# Adapter-OBD_12V5VDCDC.net
KiCad netlist of a schematic drawn in EasyEDA
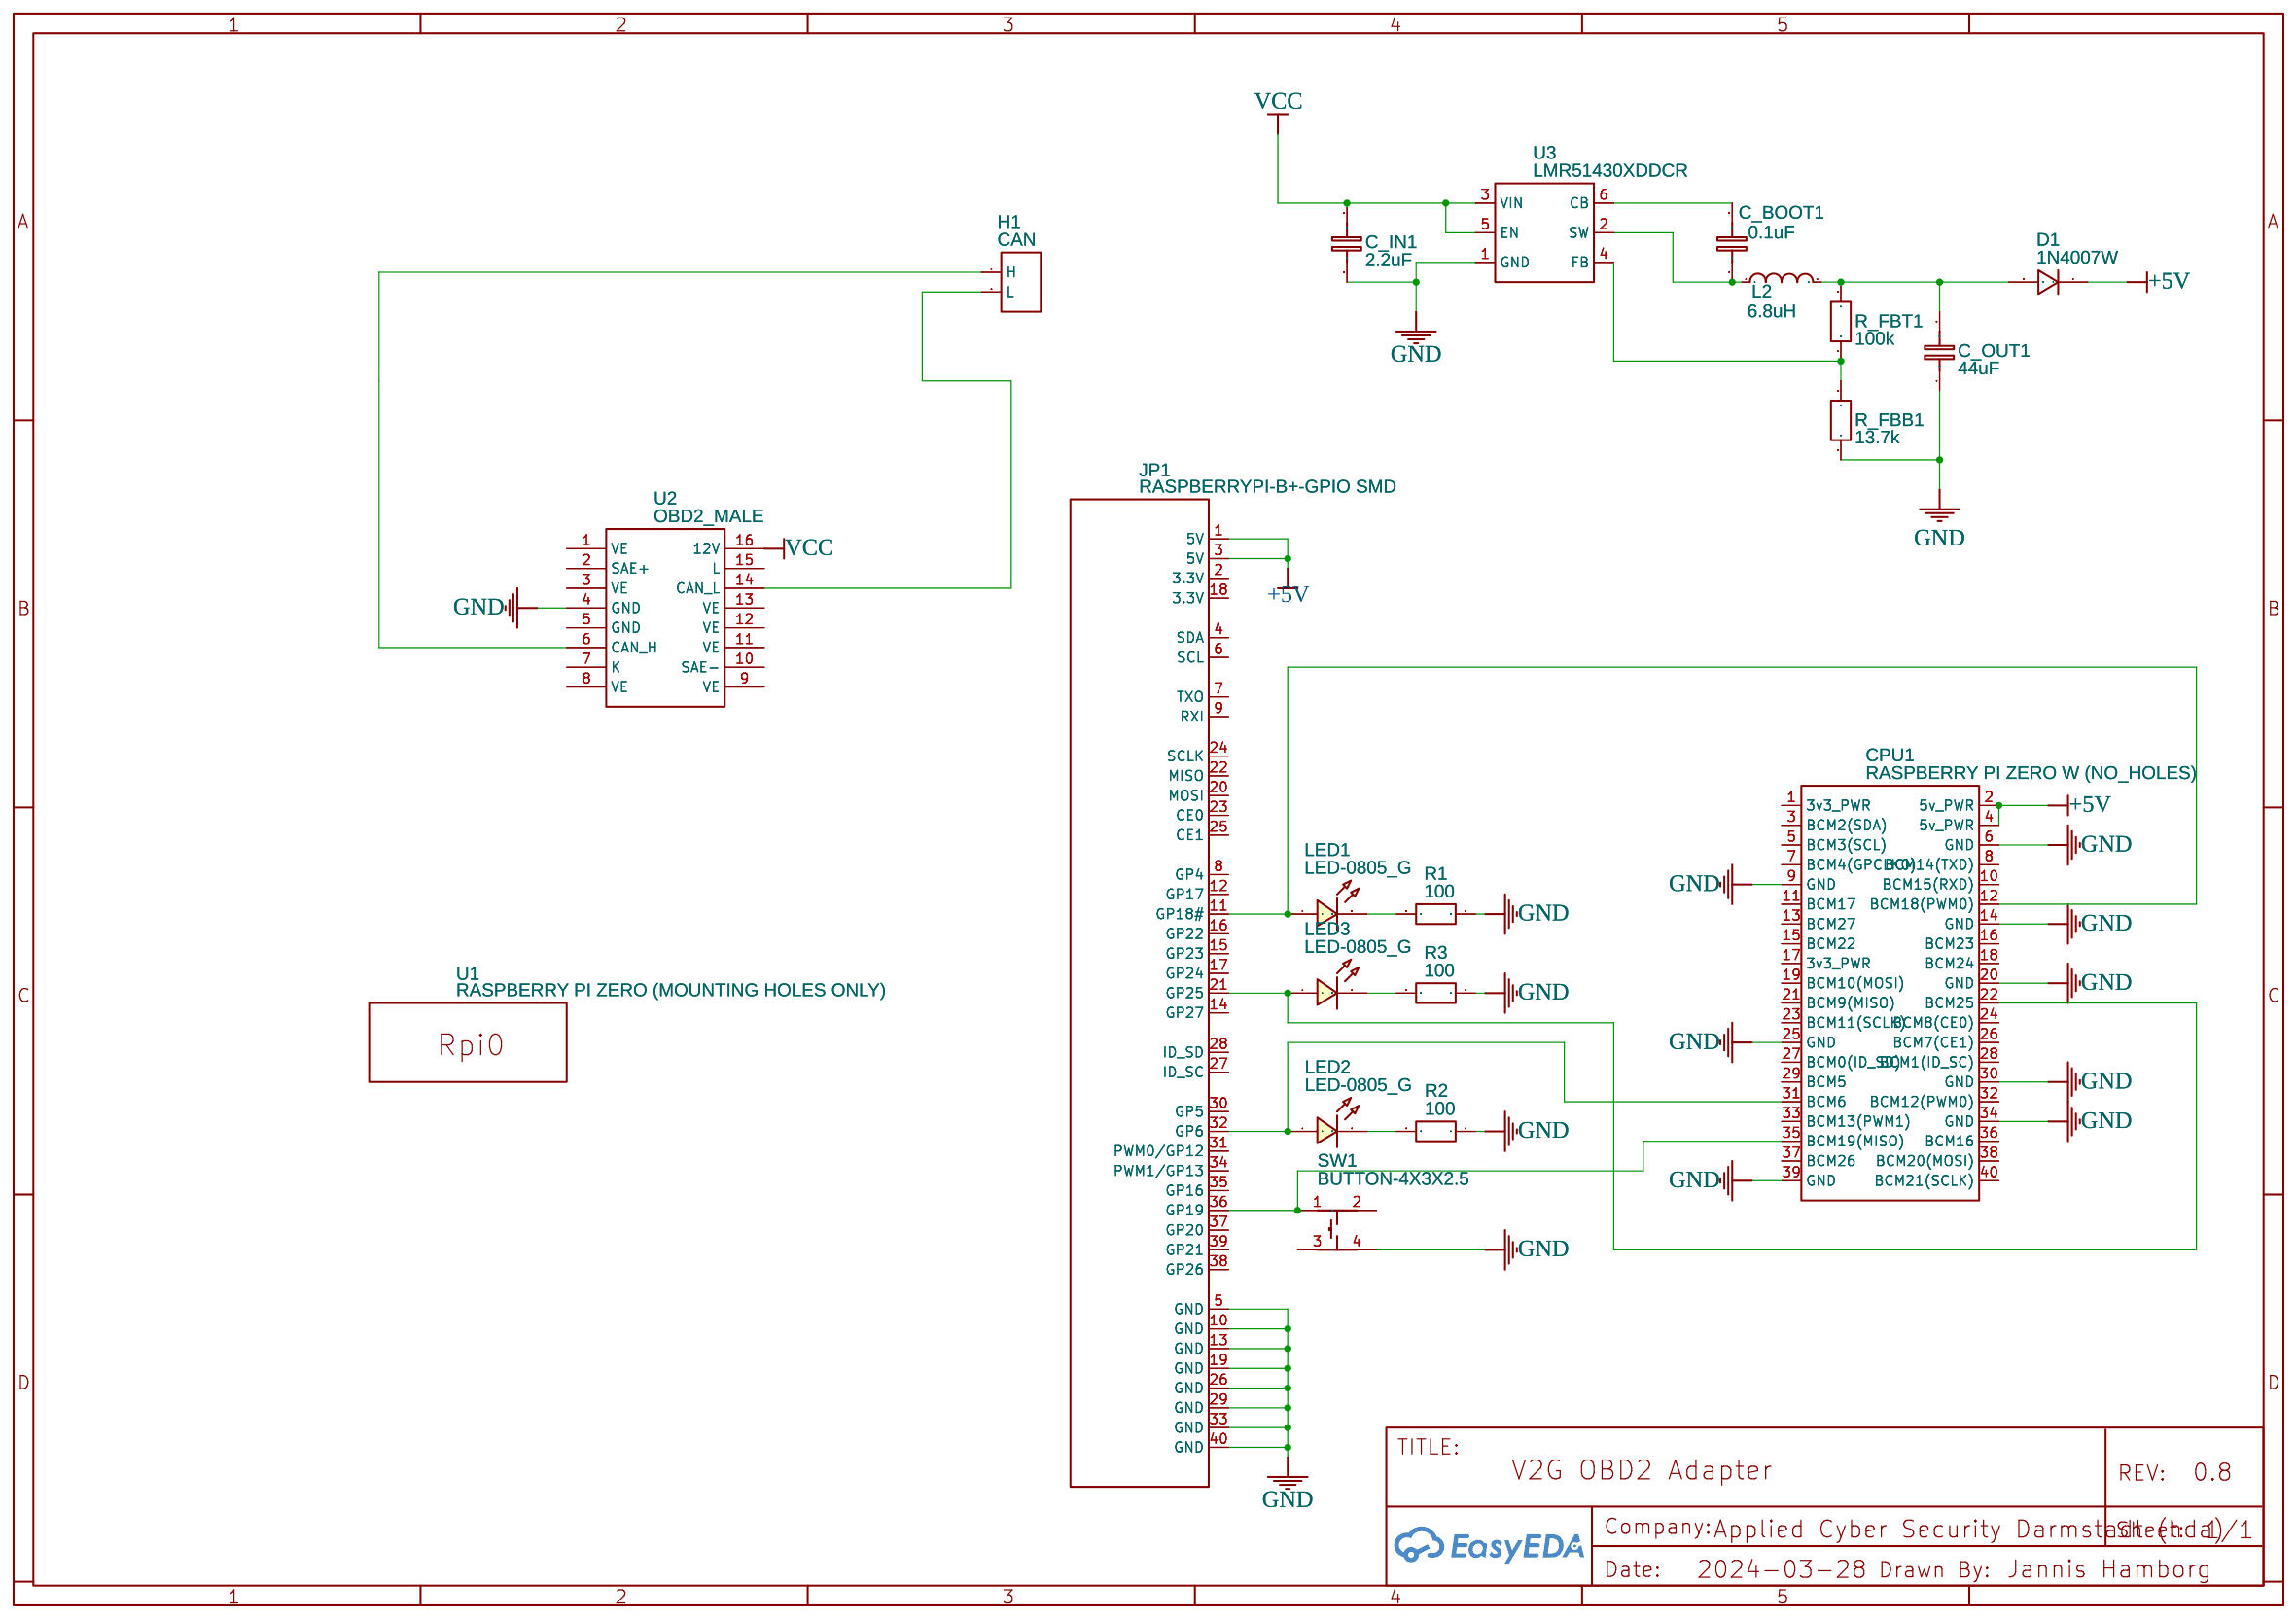
[diagram p0: schematic sheet]

(export (version "E")
  (design (tool "Eeschema 10.0.6"))
  (components
    (comp (ref "CPU1")
      (value "RASPBERRY PI ZERO W (NO_HOLES)")
      (fields (field (name "Manufacturer Part") "Pi Zero W") (field (name "Manufacturer") "Raspberry Pi"))
      (libsource (lib "") (part "RASPBERRY PI ZERO W (NO_HOLES)"))
    )
    (comp (ref "C_BOOT1") (value "0.1uF") (libsource (lib "") (part "C_0805_EU")))
    (comp (ref "C_IN1") (value "2.2uF") (libsource (lib "") (part "C_0805_EU_2")))
    (comp (ref "C_OUT1") (value "44uF") (libsource (lib "") (part "C_0805_EU_1")))
    (comp (ref "D1")
      (value "1N4007W")
      (fields (field (name "Manufacturer") "BLUE ROCKET"))
      (libsource (lib "") (part "1N4007W"))
    )
    (comp (ref "H1") (value "CAN") (libsource (lib "") (part "HDR-F-2.54_1x2")))
    (comp (ref "JP1")
      (value "RASPBERRYPI-B+-GPIO SMD")
      (fields
        (field (name "Manufacturer Part") "95157-440LF")
        (field (name "Manufacturer") "Amphenol ICC (FCI)")
      )
      (libsource (lib "") (part "RASPBERRYPI-B+-GPIO SMD"))
    )
    (comp (ref "L2")
      (value "6.8uH")
      (fields (field (name "Manufacturer Part") "FHW0805UF6R8JST") (field (name "Manufacturer") "FH(风华)"))
      (libsource (lib "") (part "FHW0805UF6R8JST"))
    )
    (comp (ref "LED1")
      (value "LED-0805_G")
      (fields (field (name "Manufacturer Part") "NCD0805G1") (field (name "Manufacturer") "国星光电"))
      (libsource (lib "") (part "LED-0805_G"))
    )
    (comp (ref "LED2")
      (value "LED-0805_G")
      (fields (field (name "Manufacturer Part") "NCD0805G1") (field (name "Manufacturer") "国星光电"))
      (libsource (lib "") (part "LED-0805_G"))
    )
    (comp (ref "LED3")
      (value "LED-0805_G")
      (fields (field (name "Manufacturer Part") "NCD0805G1") (field (name "Manufacturer") "国星光电"))
      (libsource (lib "") (part "LED-0805_G"))
    )
    (comp (ref "R1") (value "100") (libsource (lib "") (part "R_0805_EU_1")))
    (comp (ref "R2") (value "100") (libsource (lib "") (part "R_0805_EU")))
    (comp (ref "R3") (value "100") (libsource (lib "") (part "R_0805_EU")))
    (comp (ref "R_FBB1") (value "13.7k") (libsource (lib "") (part "R_0603_EU")))
    (comp (ref "R_FBT1") (value "100k") (libsource (lib "") (part "R_0603_EU_1")))
    (comp (ref "SW1") (value "BUTTON-4X3X2.5") (libsource (lib "") (part "BUTTON-4X3X2.5")))
    (comp (ref "U1")
      (value "RASPBERRY PI ZERO (MOUNTING HOLES ONLY)")
      (fields (field (name "Manufacturer Part") "Raspberry Pi Zero W"))
      (libsource (lib "") (part "RASPBERRY PI ZERO (MOUNTING HOLES ONLY)"))
    )
    (comp (ref "U2") (value "OBD2_MALE") (libsource (lib "") (part "OBD2_MALE")))
    (comp (ref "U3") (value "LMR51430XDDCR") (libsource (lib "") (part "LMR51430XDDCR")))
  )
  (nets
    (net (code "1") (name "+5V") (class "Default")
      (node (ref "CPU1") (pin "2") (pinfunction "5v_PWR_2") (pintype "unspecified"))
      (node (ref "CPU1") (pin "4") (pinfunction "5v_PWR_4") (pintype "unspecified"))
      (node (ref "D1") (pin "1") (pinfunction "1_1") (pintype "unspecified"))
      (node (ref "JP1") (pin "1") (pinfunction "5V_1") (pintype "passive"))
      (node (ref "JP1") (pin "3") (pinfunction "5V_3") (pintype "passive"))
    )
    (net (code "2") (name "GND") (class "Default")
      (node (ref "CPU1") (pin "14") (pinfunction "GND_14") (pintype "unspecified"))
      (node (ref "CPU1") (pin "20") (pinfunction "GND_20") (pintype "unspecified"))
      (node (ref "CPU1") (pin "25") (pinfunction "GND_25") (pintype "unspecified"))
      (node (ref "CPU1") (pin "30") (pinfunction "GND_30") (pintype "unspecified"))
      (node (ref "CPU1") (pin "34") (pinfunction "GND_34") (pintype "unspecified"))
      (node (ref "CPU1") (pin "39") (pinfunction "GND_39") (pintype "unspecified"))
      (node (ref "CPU1") (pin "6") (pinfunction "GND_6") (pintype "unspecified"))
      (node (ref "CPU1") (pin "9") (pinfunction "GND_9") (pintype "unspecified"))
      (node (ref "C_IN1") (pin "1") (pinfunction "1_1") (pintype "unspecified"))
      (node (ref "C_OUT1") (pin "1") (pinfunction "1_1") (pintype "unspecified"))
      (node (ref "JP1") (pin "10") (pinfunction "GND_10") (pintype "passive"))
      (node (ref "JP1") (pin "13") (pinfunction "GND_13") (pintype "passive"))
      (node (ref "JP1") (pin "19") (pinfunction "GND_19") (pintype "passive"))
      (node (ref "JP1") (pin "26") (pinfunction "GND_26") (pintype "passive"))
      (node (ref "JP1") (pin "29") (pinfunction "GND_29") (pintype "passive"))
      (node (ref "JP1") (pin "33") (pinfunction "GND_33") (pintype "passive"))
      (node (ref "JP1") (pin "40") (pinfunction "GND_40") (pintype "passive"))
      (node (ref "JP1") (pin "5") (pinfunction "GND_5") (pintype "passive"))
      (node (ref "R1") (pin "2") (pinfunction "2_2") (pintype "unspecified"))
      (node (ref "R2") (pin "1") (pinfunction "1_1") (pintype "unspecified"))
      (node (ref "R3") (pin "1") (pinfunction "1_1") (pintype "unspecified"))
      (node (ref "R_FBB1") (pin "1") (pinfunction "1_1") (pintype "unspecified"))
      (node (ref "SW1") (pin "4") (pinfunction "4_4") (pintype "unspecified"))
      (node (ref "U2") (pin "4") (pinfunction "GND_4") (pintype "unspecified"))
      (node (ref "U3") (pin "1") (pinfunction "GND_1") (pintype "unspecified"))
    )
    (net (code "3") (name "Net-(CPU1-BCM6)") (class "Default")
      (node (ref "CPU1") (pin "31") (pinfunction "BCM6_31") (pintype "unspecified"))
      (node (ref "JP1") (pin "32") (pinfunction "GP6_32") (pintype "unspecified"))
      (node (ref "LED2") (pin "1") (pinfunction "1_1") (pintype "unspecified"))
    )
    (net (code "4") (name "Net-(CPU1-BCM18(PWM0))") (class "Default")
      (node (ref "CPU1") (pin "12") (pinfunction "BCM18(PWM0)_12") (pintype "unspecified"))
      (node (ref "JP1") (pin "11") (pinfunction "GP18#_11") (pintype "unspecified"))
      (node (ref "LED1") (pin "1") (pinfunction "1_1") (pintype "unspecified"))
    )
    (net (code "5") (name "Net-(CPU1-BCM19(MISO))") (class "Default")
      (node (ref "CPU1") (pin "35") (pinfunction "BCM19(MISO)_35") (pintype "unspecified"))
      (node (ref "JP1") (pin "36") (pinfunction "GP19_36") (pintype "unspecified"))
      (node (ref "SW1") (pin "1") (pinfunction "1_1") (pintype "unspecified"))
    )
    (net (code "6") (name "Net-(CPU1-BCM25)") (class "Default")
      (node (ref "CPU1") (pin "22") (pinfunction "BCM25_22") (pintype "unspecified"))
      (node (ref "JP1") (pin "21") (pinfunction "GP25_21") (pintype "unspecified"))
      (node (ref "LED3") (pin "1") (pinfunction "1_1") (pintype "unspecified"))
    )
    (net (code "7") (name "Net-(C_OUT1-Pad2)") (class "Default")
      (node (ref "C_OUT1") (pin "2") (pinfunction "2_2") (pintype "unspecified"))
      (node (ref "D1") (pin "2") (pinfunction "2_2") (pintype "unspecified"))
      (node (ref "L2") (pin "2") (pinfunction "2_2") (pintype "unspecified"))
      (node (ref "R_FBT1") (pin "2") (pinfunction "2_2") (pintype "unspecified"))
    )
    (net (code "8") (name "Net-(H1-H)") (class "Default")
      (node (ref "H1") (pin "1") (pinfunction "H_1") (pintype "input"))
      (node (ref "U2") (pin "6") (pinfunction "CAN_H_6") (pintype "unspecified"))
    )
    (net (code "9") (name "Net-(H1-L)") (class "Default")
      (node (ref "H1") (pin "2") (pinfunction "L_2") (pintype "input"))
      (node (ref "U2") (pin "14") (pinfunction "CAN_L_14") (pintype "unspecified"))
    )
    (net (code "10") (name "Net-(LED1-Pad2)") (class "Default")
      (node (ref "LED1") (pin "2") (pinfunction "2_2") (pintype "unspecified"))
      (node (ref "R1") (pin "1") (pinfunction "1_1") (pintype "unspecified"))
    )
    (net (code "11") (name "Net-(LED2-Pad2)") (class "Default")
      (node (ref "LED2") (pin "2") (pinfunction "2_2") (pintype "unspecified"))
      (node (ref "R2") (pin "2") (pinfunction "2_2") (pintype "unspecified"))
    )
    (net (code "12") (name "Net-(LED3-Pad2)") (class "Default")
      (node (ref "LED3") (pin "2") (pinfunction "2_2") (pintype "unspecified"))
      (node (ref "R3") (pin "2") (pinfunction "2_2") (pintype "unspecified"))
    )
    (net (code "13") (name "Net-(U3-CB)") (class "Default")
      (node (ref "C_BOOT1") (pin "2") (pinfunction "2_2") (pintype "unspecified"))
      (node (ref "U3") (pin "6") (pinfunction "CB_6") (pintype "unspecified"))
    )
    (net (code "14") (name "Net-(U3-FB)") (class "Default")
      (node (ref "R_FBB1") (pin "2") (pinfunction "2_2") (pintype "unspecified"))
      (node (ref "R_FBT1") (pin "1") (pinfunction "1_1") (pintype "unspecified"))
      (node (ref "U3") (pin "4") (pinfunction "FB_4") (pintype "unspecified"))
    )
    (net (code "15") (name "Net-(U3-SW)") (class "Default")
      (node (ref "C_BOOT1") (pin "1") (pinfunction "1_1") (pintype "unspecified"))
      (node (ref "L2") (pin "1") (pinfunction "1_1") (pintype "unspecified"))
      (node (ref "U3") (pin "2") (pinfunction "SW_2") (pintype "unspecified"))
    )
    (net (code "16") (name "VCC") (class "Default")
      (node (ref "C_IN1") (pin "2") (pinfunction "2_2") (pintype "unspecified"))
      (node (ref "U2") (pin "16") (pinfunction "12V_16") (pintype "unspecified"))
      (node (ref "U3") (pin "3") (pinfunction "VIN_3") (pintype "unspecified"))
      (node (ref "U3") (pin "5") (pinfunction "EN_5") (pintype "unspecified"))
    )
    (net (code "17") (name "unconnected-(CPU1-3v3_PWR-Pad1)") (class "Default")
      (node (ref "CPU1") (pin "1") (pinfunction "3v3_PWR_1") (pintype "passive"))
    )
    (net (code "18") (name "unconnected-(CPU1-3v3_PWR-Pad17)") (class "Default")
      (node (ref "CPU1") (pin "17") (pinfunction "3v3_PWR_17") (pintype "unspecified"))
    )
    (net (code "19") (name "unconnected-(CPU1-BCM0(ID_SD)-Pad27)") (class "Default")
      (node (ref "CPU1") (pin "27") (pinfunction "BCM0(ID_SD)_27") (pintype "unspecified"))
    )
    (net (code "20") (name "unconnected-(CPU1-BCM1(ID_SC)-Pad28)") (class "Default")
      (node (ref "CPU1") (pin "28") (pinfunction "BCM1(ID_SC)_28") (pintype "unspecified"))
    )
    (net (code "21") (name "unconnected-(CPU1-BCM2(SDA)-Pad3)") (class "Default")
      (node (ref "CPU1") (pin "3") (pinfunction "BCM2(SDA)_3") (pintype "unspecified"))
    )
    (net (code "22") (name "unconnected-(CPU1-BCM3(SCL)-Pad5)") (class "Default")
      (node (ref "CPU1") (pin "5") (pinfunction "BCM3(SCL)_5") (pintype "unspecified"))
    )
    (net (code "23") (name "unconnected-(CPU1-BCM4(GPCLK0)-Pad7)") (class "Default")
      (node (ref "CPU1") (pin "7") (pinfunction "BCM4(GPCLK0)_7") (pintype "unspecified"))
    )
    (net (code "24") (name "unconnected-(CPU1-BCM5-Pad29)") (class "Default")
      (node (ref "CPU1") (pin "29") (pinfunction "BCM5_29") (pintype "unspecified"))
    )
    (net (code "25") (name "unconnected-(CPU1-BCM7(CE1)-Pad26)") (class "Default")
      (node (ref "CPU1") (pin "26") (pinfunction "BCM7(CE1)_26") (pintype "unspecified"))
    )
    (net (code "26") (name "unconnected-(CPU1-BCM8(CE0)-Pad24)") (class "Default")
      (node (ref "CPU1") (pin "24") (pinfunction "BCM8(CE0)_24") (pintype "unspecified"))
    )
    (net (code "27") (name "unconnected-(CPU1-BCM9(MISO)-Pad21)") (class "Default")
      (node (ref "CPU1") (pin "21") (pinfunction "BCM9(MISO)_21") (pintype "unspecified"))
    )
    (net (code "28") (name "unconnected-(CPU1-BCM10(MOSI)-Pad19)") (class "Default")
      (node (ref "CPU1") (pin "19") (pinfunction "BCM10(MOSI)_19") (pintype "unspecified"))
    )
    (net (code "29") (name "unconnected-(CPU1-BCM11(SCLK)-Pad23)") (class "Default")
      (node (ref "CPU1") (pin "23") (pinfunction "BCM11(SCLK)_23") (pintype "unspecified"))
    )
    (net (code "30") (name "unconnected-(CPU1-BCM12(PWM0)-Pad32)") (class "Default")
      (node (ref "CPU1") (pin "32") (pinfunction "BCM12(PWM0)_32") (pintype "unspecified"))
    )
    (net (code "31") (name "unconnected-(CPU1-BCM13(PWM1)-Pad33)") (class "Default")
      (node (ref "CPU1") (pin "33") (pinfunction "BCM13(PWM1)_33") (pintype "unspecified"))
    )
    (net (code "32") (name "unconnected-(CPU1-BCM14(TXD)-Pad8)") (class "Default")
      (node (ref "CPU1") (pin "8") (pinfunction "BCM14(TXD)_8") (pintype "unspecified"))
    )
    (net (code "33") (name "unconnected-(CPU1-BCM15(RXD)-Pad10)") (class "Default")
      (node (ref "CPU1") (pin "10") (pinfunction "BCM15(RXD)_10") (pintype "unspecified"))
    )
    (net (code "34") (name "unconnected-(CPU1-BCM16-Pad36)") (class "Default")
      (node (ref "CPU1") (pin "36") (pinfunction "BCM16_36") (pintype "unspecified"))
    )
    (net (code "35") (name "unconnected-(CPU1-BCM17-Pad11)") (class "Default")
      (node (ref "CPU1") (pin "11") (pinfunction "BCM17_11") (pintype "unspecified"))
    )
    (net (code "36") (name "unconnected-(CPU1-BCM20(MOSI)-Pad38)") (class "Default")
      (node (ref "CPU1") (pin "38") (pinfunction "BCM20(MOSI)_38") (pintype "unspecified"))
    )
    (net (code "37") (name "unconnected-(CPU1-BCM21(SCLK)-Pad40)") (class "Default")
      (node (ref "CPU1") (pin "40") (pinfunction "BCM21(SCLK)_40") (pintype "unspecified"))
    )
    (net (code "38") (name "unconnected-(CPU1-BCM22-Pad15)") (class "Default")
      (node (ref "CPU1") (pin "15") (pinfunction "BCM22_15") (pintype "unspecified"))
    )
    (net (code "39") (name "unconnected-(CPU1-BCM23-Pad16)") (class "Default")
      (node (ref "CPU1") (pin "16") (pinfunction "BCM23_16") (pintype "unspecified"))
    )
    (net (code "40") (name "unconnected-(CPU1-BCM24-Pad18)") (class "Default")
      (node (ref "CPU1") (pin "18") (pinfunction "BCM24_18") (pintype "unspecified"))
    )
    (net (code "41") (name "unconnected-(CPU1-BCM26-Pad37)") (class "Default")
      (node (ref "CPU1") (pin "37") (pinfunction "BCM26_37") (pintype "unspecified"))
    )
    (net (code "42") (name "unconnected-(CPU1-BCM27-Pad13)") (class "Default")
      (node (ref "CPU1") (pin "13") (pinfunction "BCM27_13") (pintype "unspecified"))
    )
    (net (code "43") (name "unconnected-(JP1-3.3V-Pad2)") (class "Default")
      (node (ref "JP1") (pin "2") (pinfunction "3.3V_2") (pintype "passive"))
    )
    (net (code "44") (name "unconnected-(JP1-3.3V-Pad18)") (class "Default")
      (node (ref "JP1") (pin "18") (pinfunction "3.3V_18") (pintype "passive"))
    )
    (net (code "45") (name "unconnected-(JP1-CE0-Pad23)") (class "Default")
      (node (ref "JP1") (pin "23") (pinfunction "CE0_23") (pintype "output"))
    )
    (net (code "46") (name "unconnected-(JP1-CE1-Pad25)") (class "Default")
      (node (ref "JP1") (pin "25") (pinfunction "CE1_25") (pintype "output"))
    )
    (net (code "47") (name "unconnected-(JP1-GP4-Pad8)") (class "Default")
      (node (ref "JP1") (pin "8") (pinfunction "GP4_8") (pintype "unspecified"))
    )
    (net (code "48") (name "unconnected-(JP1-GP5-Pad30)") (class "Default")
      (node (ref "JP1") (pin "30") (pinfunction "GP5_30") (pintype "unspecified"))
    )
    (net (code "49") (name "unconnected-(JP1-GP16-Pad35)") (class "Default")
      (node (ref "JP1") (pin "35") (pinfunction "GP16_35") (pintype "unspecified"))
    )
    (net (code "50") (name "unconnected-(JP1-GP17-Pad12)") (class "Default")
      (node (ref "JP1") (pin "12") (pinfunction "GP17_12") (pintype "unspecified"))
    )
    (net (code "51") (name "unconnected-(JP1-GP20-Pad37)") (class "Default")
      (node (ref "JP1") (pin "37") (pinfunction "GP20_37") (pintype "unspecified"))
    )
    (net (code "52") (name "unconnected-(JP1-GP21-Pad39)") (class "Default")
      (node (ref "JP1") (pin "39") (pinfunction "GP21_39") (pintype "unspecified"))
    )
    (net (code "53") (name "unconnected-(JP1-GP22-Pad16)") (class "Default")
      (node (ref "JP1") (pin "16") (pinfunction "GP22_16") (pintype "unspecified"))
    )
    (net (code "54") (name "unconnected-(JP1-GP23-Pad15)") (class "Default")
      (node (ref "JP1") (pin "15") (pinfunction "GP23_15") (pintype "unspecified"))
    )
    (net (code "55") (name "unconnected-(JP1-GP24-Pad17)") (class "Default")
      (node (ref "JP1") (pin "17") (pinfunction "GP24_17") (pintype "unspecified"))
    )
    (net (code "56") (name "unconnected-(JP1-GP26-Pad38)") (class "Default")
      (node (ref "JP1") (pin "38") (pinfunction "GP26_38") (pintype "unspecified"))
    )
    (net (code "57") (name "unconnected-(JP1-GP27-Pad14)") (class "Default")
      (node (ref "JP1") (pin "14") (pinfunction "GP27_14") (pintype "unspecified"))
    )
    (net (code "58") (name "unconnected-(JP1-ID_SC-Pad27)") (class "Default")
      (node (ref "JP1") (pin "27") (pinfunction "ID_SC_27") (pintype "unspecified"))
    )
    (net (code "59") (name "unconnected-(JP1-ID_SD-Pad28)") (class "Default")
      (node (ref "JP1") (pin "28") (pinfunction "ID_SD_28") (pintype "unspecified"))
    )
    (net (code "60") (name "unconnected-(JP1-MISO-Pad22)") (class "Default")
      (node (ref "JP1") (pin "22") (pinfunction "MISO_22") (pintype "input"))
    )
    (net (code "61") (name "unconnected-(JP1-MOSI-Pad20)") (class "Default")
      (node (ref "JP1") (pin "20") (pinfunction "MOSI_20") (pintype "output"))
    )
    (net (code "62") (name "unconnected-(JP1-PWM0{slash}GP12-Pad31)") (class "Default")
      (node (ref "JP1") (pin "31") (pinfunction "PWM0/GP12_31") (pintype "unspecified"))
    )
    (net (code "63") (name "unconnected-(JP1-PWM1{slash}GP13-Pad34)") (class "Default")
      (node (ref "JP1") (pin "34") (pinfunction "PWM1/GP13_34") (pintype "unspecified"))
    )
    (net (code "64") (name "unconnected-(JP1-RXI-Pad9)") (class "Default")
      (node (ref "JP1") (pin "9") (pinfunction "RXI_9") (pintype "input"))
    )
    (net (code "65") (name "unconnected-(JP1-SCL-Pad6)") (class "Default")
      (node (ref "JP1") (pin "6") (pinfunction "SCL_6") (pintype "unspecified"))
    )
    (net (code "66") (name "unconnected-(JP1-SCLK-Pad24)") (class "Default")
      (node (ref "JP1") (pin "24") (pinfunction "SCLK_24") (pintype "output"))
    )
    (net (code "67") (name "unconnected-(JP1-SDA-Pad4)") (class "Default")
      (node (ref "JP1") (pin "4") (pinfunction "SDA_4") (pintype "unspecified"))
    )
    (net (code "68") (name "unconnected-(JP1-TXO-Pad7)") (class "Default")
      (node (ref "JP1") (pin "7") (pinfunction "TXO_7") (pintype "output"))
    )
    (net (code "69") (name "unconnected-(SW1-Pad2)") (class "Default")
      (node (ref "SW1") (pin "2") (pinfunction "2_2") (pintype "unspecified"))
    )
    (net (code "70") (name "unconnected-(SW1-Pad3)") (class "Default")
      (node (ref "SW1") (pin "3") (pinfunction "3_3") (pintype "unspecified"))
    )
    (net (code "71") (name "unconnected-(U2-GND-Pad5)") (class "Default")
      (node (ref "U2") (pin "5") (pinfunction "GND_5") (pintype "unspecified"))
    )
    (net (code "72") (name "unconnected-(U2-K-Pad7)") (class "Default")
      (node (ref "U2") (pin "7") (pinfunction "K_7") (pintype "unspecified"))
    )
    (net (code "73") (name "unconnected-(U2-L-Pad15)") (class "Default")
      (node (ref "U2") (pin "15") (pinfunction "L_15") (pintype "unspecified"))
    )
    (net (code "74") (name "unconnected-(U2-SAE+-Pad2)") (class "Default")
      (node (ref "U2") (pin "2") (pinfunction "SAE+_2") (pintype "unspecified"))
    )
    (net (code "75") (name "unconnected-(U2-SAE--Pad10)") (class "Default")
      (node (ref "U2") (pin "10") (pinfunction "SAE-_10") (pintype "unspecified"))
    )
    (net (code "76") (name "unconnected-(U2-VE-Pad1)") (class "Default")
      (node (ref "U2") (pin "1") (pinfunction "VE_1") (pintype "unspecified"))
    )
    (net (code "77") (name "unconnected-(U2-VE-Pad3)") (class "Default")
      (node (ref "U2") (pin "3") (pinfunction "VE_3") (pintype "unspecified"))
    )
    (net (code "78") (name "unconnected-(U2-VE-Pad8)") (class "Default")
      (node (ref "U2") (pin "8") (pinfunction "VE_8") (pintype "unspecified"))
    )
    (net (code "79") (name "unconnected-(U2-VE-Pad9)") (class "Default")
      (node (ref "U2") (pin "9") (pinfunction "VE_9") (pintype "unspecified"))
    )
    (net (code "80") (name "unconnected-(U2-VE-Pad11)") (class "Default")
      (node (ref "U2") (pin "11") (pinfunction "VE_11") (pintype "unspecified"))
    )
    (net (code "81") (name "unconnected-(U2-VE-Pad12)") (class "Default")
      (node (ref "U2") (pin "12") (pinfunction "VE_12") (pintype "unspecified"))
    )
    (net (code "82") (name "unconnected-(U2-VE-Pad13)") (class "Default")
      (node (ref "U2") (pin "13") (pinfunction "VE_13") (pintype "unspecified"))
    )
  )
)
